# RTC_pb.net
KiCad netlist of a schematic drawn in EAGLE
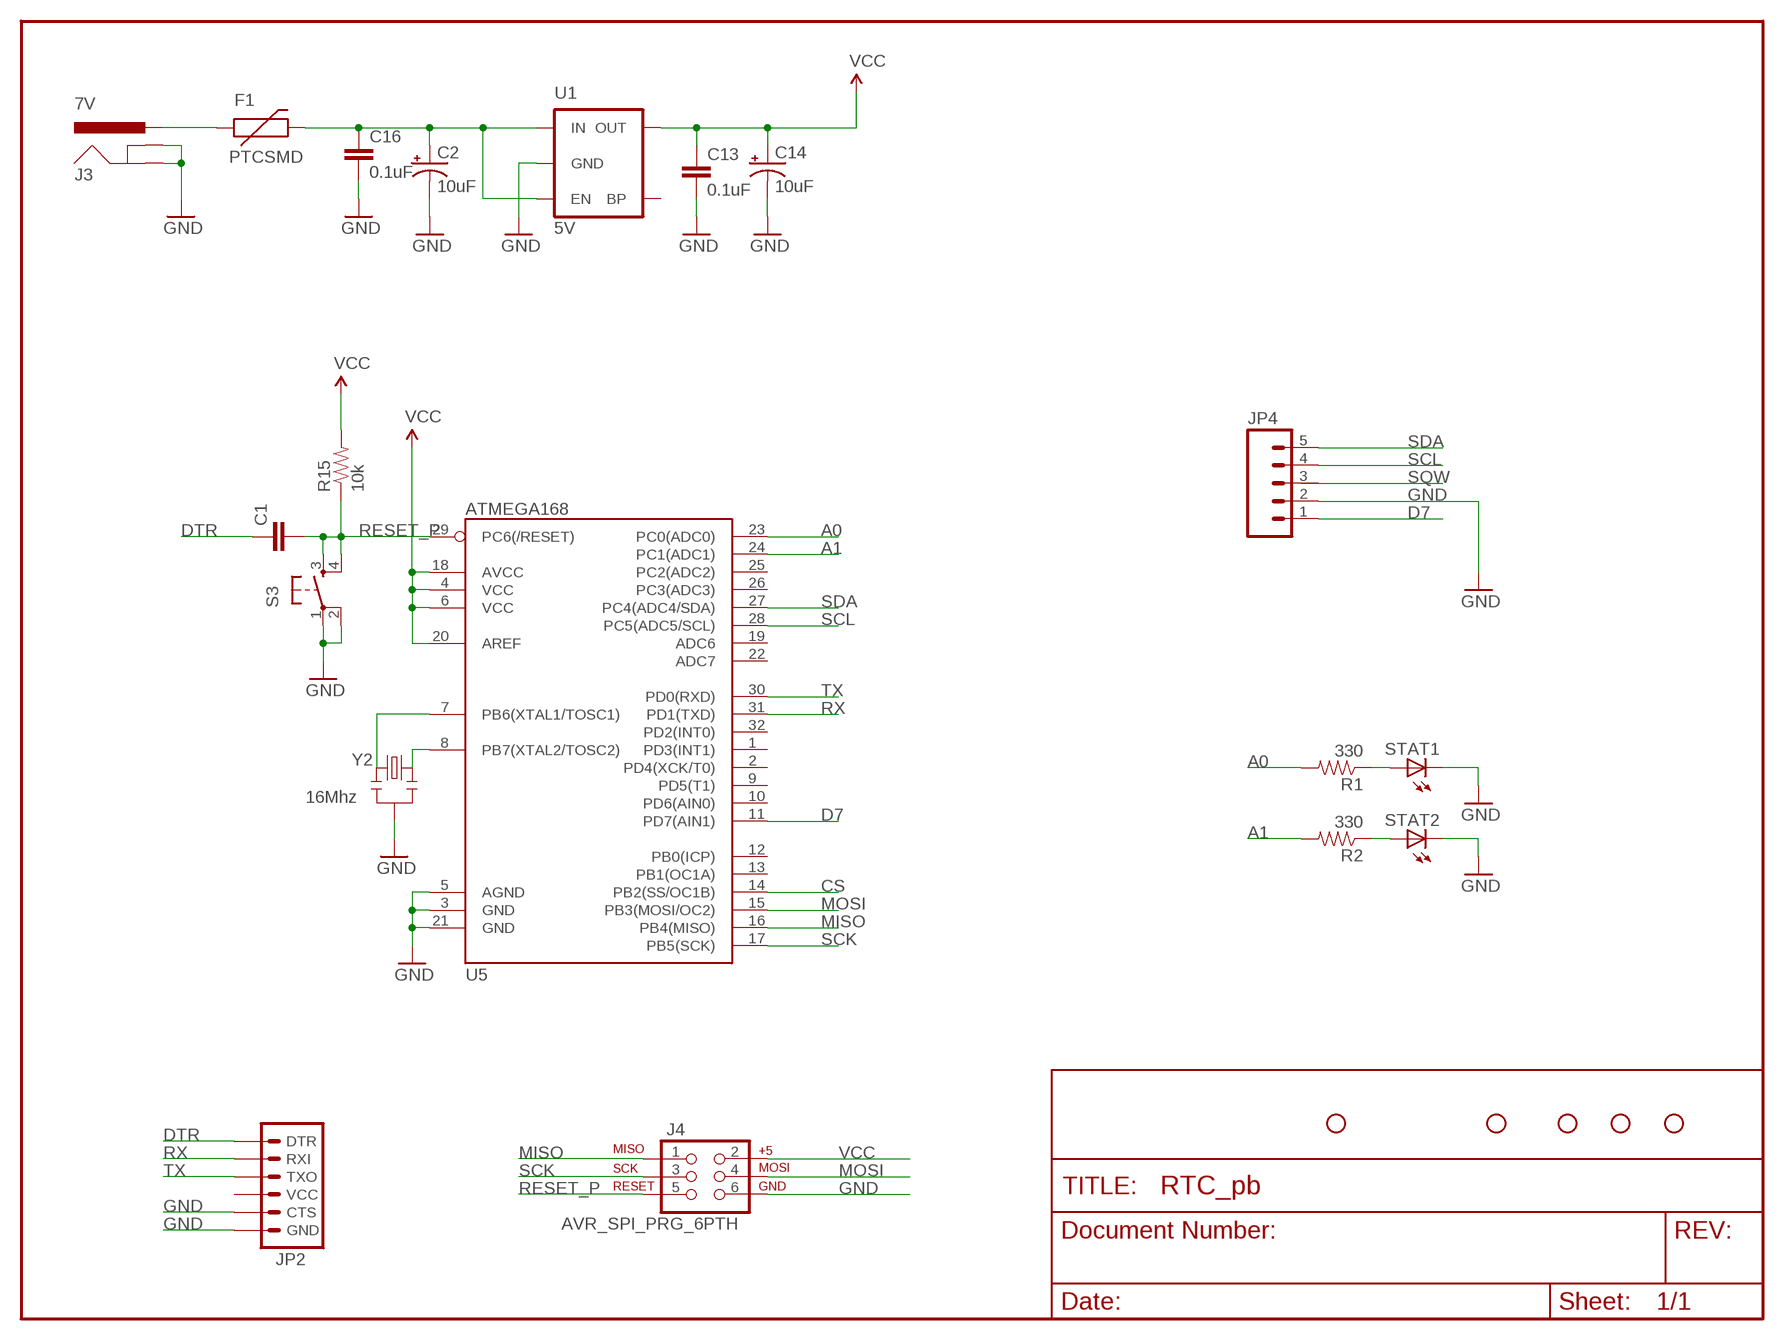
[diagram p0: schematic, sheet 1]

(export (version "E")
  (design (tool "Eeschema 10.0.6"))
  (components
    (comp (ref "C1")
      (value "CAP0603-CAP")
      (footprint "eagle-import:0603-CAP")
      (libsource (lib "eagle-import") (part "CAP0603-CAP"))
    )
    (comp (ref "C2")
      (value "10uF")
      (footprint "eagle-import:EIA3216")
      (libsource (lib "eagle-import") (part "CAP_POL1206"))
    )
    (comp (ref "C13")
      (value "0.1uF")
      (footprint "eagle-import:0603-CAP")
      (libsource (lib "eagle-import") (part "CAP0603-CAP"))
    )
    (comp (ref "C14")
      (value "10uF")
      (footprint "eagle-import:EIA3216")
      (libsource (lib "eagle-import") (part "CAP_POL1206"))
    )
    (comp (ref "C16")
      (value "0.1uF")
      (footprint "eagle-import:0603-CAP")
      (libsource (lib "eagle-import") (part "CAP0603-CAP"))
    )
    (comp (ref "F1")
      (value "PTCSMD")
      (footprint "eagle-import:PTC-1206")
      (libsource (lib "eagle-import") (part "PTCSMD"))
    )
    (comp (ref "J3")
      (value "7V")
      (footprint "eagle-import:POWER_JACK_PTH_LOCK")
      (libsource (lib "eagle-import") (part "POWER_JACKPTH_LOCK"))
    )
    (comp (ref "J4")
      (value "AVR_SPI_PRG_6PTH")
      (footprint "eagle-import:2X3")
      (libsource (lib "eagle-import") (part "AVR_SPI_PRG_6PTH"))
    )
    (comp (ref "JP1")
      (value "STAND-OFFTIGHT")
      (footprint "eagle-import:STAND-OFF-TIGHT")
      (libsource (lib "eagle-import") (part "STAND-OFFTIGHT"))
    )
    (comp (ref "JP2")
      (value "ARDUINO_SERIAL_PROGRAMPTH")
      (footprint "eagle-import:1X06")
      (libsource (lib "eagle-import") (part "ARDUINO_SERIAL_PROGRAMPTH"))
    )
    (comp (ref "JP4")
      (value "M05PTH_LONGPADS")
      (footprint "eagle-import:1X05_LONGPADS")
      (libsource (lib "eagle-import") (part "M05PTH_LONGPADS"))
    )
    (comp (ref "JP7")
      (value "STAND-OFFTIGHT")
      (footprint "eagle-import:STAND-OFF-TIGHT")
      (libsource (lib "eagle-import") (part "STAND-OFFTIGHT"))
    )
    (comp (ref "JP8")
      (value "STAND-OFFTIGHT")
      (footprint "eagle-import:STAND-OFF-TIGHT")
      (libsource (lib "eagle-import") (part "STAND-OFFTIGHT"))
    )
    (comp (ref "JP9")
      (value "STAND-OFFTIGHT")
      (footprint "eagle-import:STAND-OFF-TIGHT")
      (libsource (lib "eagle-import") (part "STAND-OFFTIGHT"))
    )
    (comp (ref "JP10")
      (value "STAND-OFFTIGHT")
      (footprint "eagle-import:STAND-OFF-TIGHT")
      (libsource (lib "eagle-import") (part "STAND-OFFTIGHT"))
    )
    (comp (ref "R1")
      (value "330")
      (footprint "eagle-import:0603-RES")
      (libsource (lib "eagle-import") (part "RESISTOR0603-RES"))
    )
    (comp (ref "R2")
      (value "330")
      (footprint "eagle-import:0603-RES")
      (libsource (lib "eagle-import") (part "RESISTOR0603-RES"))
    )
    (comp (ref "R15")
      (value "10k")
      (footprint "eagle-import:0603-RES")
      (libsource (lib "eagle-import") (part "RESISTOR0603-RES"))
    )
    (comp (ref "S3")
      (value "TAC_SWITCHPTH")
      (footprint "eagle-import:TACTILE-PTH")
      (libsource (lib "eagle-import") (part "TAC_SWITCHPTH"))
    )
    (comp (ref "STAT1")
      (value "Yellow")
      (footprint "eagle-import:LED-1206")
      (libsource (lib "eagle-import") (part "LED1206"))
    )
    (comp (ref "STAT2")
      (value "Yellow")
      (footprint "eagle-import:LED-1206")
      (libsource (lib "eagle-import") (part "LED1206"))
    )
    (comp (ref "U1")
      (value "3.3V")
      (footprint "eagle-import:SOT23-5")
      (libsource (lib "eagle-import") (part "V_REG_LDOSMD"))
    )
    (comp (ref "U5")
      (value "ATMEGA168")
      (footprint "eagle-import:TQFP32-08")
      (libsource (lib "eagle-import") (part "ATMEGA168"))
    )
    (comp (ref "Y2")
      (value "8MHz")
      (footprint "eagle-import:RESONATOR-SMD")
      (libsource (lib "eagle-import") (part "RESONATORSMD"))
    )
  )
  (nets
    (net (code "1") (name "/A0") (class "Default")
      (node (ref "R1") (pin "2") (pinfunction "2_2") (pintype "passive"))
      (node (ref "U5") (pin "23") (pinfunction "PC0(ADC0)_23") (pintype "bidirectional"))
    )
    (net (code "2") (name "/A1") (class "Default")
      (node (ref "R2") (pin "2") (pinfunction "2_2") (pintype "passive"))
      (node (ref "U5") (pin "24") (pinfunction "PC1(ADC1)_24") (pintype "bidirectional"))
    )
    (net (code "3") (name "/CS") (class "Default")
      (node (ref "U5") (pin "14") (pinfunction "PB2(SS/OC1B)_14") (pintype "bidirectional"))
    )
    (net (code "4") (name "/D7") (class "Default")
      (node (ref "JP4") (pin "1") (pinfunction "1_1") (pintype "passive"))
      (node (ref "U5") (pin "11") (pinfunction "PD7(AIN1)_11") (pintype "bidirectional"))
    )
    (net (code "5") (name "/DTR") (class "Default")
      (node (ref "C1") (pin "1") (pinfunction "1_1") (pintype "passive"))
      (node (ref "JP2") (pin "1") (pinfunction "DTR_1") (pintype "passive"))
    )
    (net (code "6") (name "/MISO") (class "Default")
      (node (ref "J4") (pin "1") (pinfunction "1_1") (pintype "passive"))
      (node (ref "U5") (pin "16") (pinfunction "PB4(MISO)_16") (pintype "bidirectional"))
    )
    (net (code "7") (name "/MOSI") (class "Default")
      (node (ref "J4") (pin "4") (pinfunction "4_4") (pintype "passive"))
      (node (ref "U5") (pin "15") (pinfunction "PB3(MOSI/OC2)_15") (pintype "bidirectional"))
    )
    (net (code "8") (name "/RESET_P") (class "Default")
      (node (ref "C1") (pin "2") (pinfunction "2_2") (pintype "passive"))
      (node (ref "J4") (pin "5") (pinfunction "5_5") (pintype "passive"))
      (node (ref "R15") (pin "1") (pinfunction "1_1") (pintype "passive"))
      (node (ref "S3") (pin "3") (pinfunction "3_3") (pintype "passive"))
      (node (ref "S3") (pin "4") (pinfunction "4_4") (pintype "passive"))
      (node (ref "U5") (pin "29") (pinfunction "PC6(/RESET)_29") (pintype "bidirectional"))
    )
    (net (code "9") (name "/RX") (class "Default")
      (node (ref "JP2") (pin "2") (pinfunction "RXI_2") (pintype "passive"))
      (node (ref "U5") (pin "31") (pinfunction "PD1(TXD)_31") (pintype "bidirectional"))
    )
    (net (code "10") (name "/SCK") (class "Default")
      (node (ref "J4") (pin "3") (pinfunction "3_3") (pintype "passive"))
      (node (ref "U5") (pin "17") (pinfunction "PB5(SCK)_17") (pintype "bidirectional"))
    )
    (net (code "11") (name "/SCL") (class "Default")
      (node (ref "JP4") (pin "4") (pinfunction "4_4") (pintype "passive"))
      (node (ref "U5") (pin "28") (pinfunction "PC5(ADC5/SCL)_28") (pintype "bidirectional"))
    )
    (net (code "12") (name "/SDA") (class "Default")
      (node (ref "JP4") (pin "5") (pinfunction "5_5") (pintype "passive"))
      (node (ref "U5") (pin "27") (pinfunction "PC4(ADC4/SDA)_27") (pintype "bidirectional"))
    )
    (net (code "14") (name "/TX") (class "Default")
      (node (ref "JP2") (pin "3") (pinfunction "TXO_3") (pintype "passive"))
      (node (ref "U5") (pin "30") (pinfunction "PD0(RXD)_30") (pintype "bidirectional"))
    )
    (net (code "15") (name "GND") (class "Default")
      (node (ref "C13") (pin "2") (pinfunction "2_2") (pintype "passive"))
      (node (ref "C14") (pin "C") (pinfunction "-_C") (pintype "passive"))
      (node (ref "C16") (pin "2") (pinfunction "2_2") (pintype "passive"))
      (node (ref "C2") (pin "C") (pinfunction "-_C") (pintype "passive"))
      (node (ref "J3") (pin "GND") (pinfunction "GND_GND") (pintype "bidirectional"))
      (node (ref "J3") (pin "GNDBREAK") (pinfunction "GNDBREAK_GNDBREAK") (pintype "bidirectional"))
      (node (ref "J4") (pin "6") (pinfunction "6_6") (pintype "passive"))
      (node (ref "JP2") (pin "5") (pinfunction "CTS_5") (pintype "passive"))
      (node (ref "JP2") (pin "6") (pinfunction "GND_6") (pintype "passive"))
      (node (ref "JP4") (pin "2") (pinfunction "2_2") (pintype "passive"))
      (node (ref "S3") (pin "1") (pinfunction "1_1") (pintype "passive"))
      (node (ref "S3") (pin "2") (pinfunction "2_2") (pintype "passive"))
      (node (ref "STAT1") (pin "C") (pinfunction "C_C") (pintype "passive"))
      (node (ref "STAT2") (pin "C") (pinfunction "C_C") (pintype "passive"))
      (node (ref "U1") (pin "2") (pinfunction "GND_2") (pintype "input"))
      (node (ref "U5") (pin "21") (pinfunction "GND_21") (pintype "bidirectional"))
      (node (ref "U5") (pin "3") (pinfunction "GND_3") (pintype "bidirectional"))
      (node (ref "U5") (pin "5") (pinfunction "AGND_5") (pintype "bidirectional"))
      (node (ref "Y2") (pin "2") (pinfunction "2_2") (pintype "passive"))
    )
    (net (code "16") (name "Net-(C2-+)") (class "Default")
      (node (ref "C16") (pin "1") (pinfunction "1_1") (pintype "passive"))
      (node (ref "C2") (pin "A") (pinfunction "+_A") (pintype "passive"))
      (node (ref "F1") (pin "2") (pinfunction "2_2") (pintype "bidirectional"))
      (node (ref "U1") (pin "1") (pinfunction "IN_1") (pintype "input"))
      (node (ref "U1") (pin "3") (pinfunction "EN_3") (pintype "input"))
    )
    (net (code "17") (name "Net-(F1-Pad1)") (class "Default")
      (node (ref "F1") (pin "1") (pinfunction "1_1") (pintype "bidirectional"))
      (node (ref "J3") (pin "PWR") (pinfunction "PWR_PWR") (pintype "bidirectional"))
    )
    (net (code "18") (name "Net-(R1-Pad1)") (class "Default")
      (node (ref "R1") (pin "1") (pinfunction "1_1") (pintype "passive"))
      (node (ref "STAT1") (pin "A") (pinfunction "A_A") (pintype "passive"))
    )
    (net (code "19") (name "Net-(R2-Pad1)") (class "Default")
      (node (ref "R2") (pin "1") (pinfunction "1_1") (pintype "passive"))
      (node (ref "STAT2") (pin "A") (pinfunction "A_A") (pintype "passive"))
    )
    (net (code "20") (name "Net-(U5-PB6(XTAL1{slash}TOSC1))") (class "Default")
      (node (ref "U5") (pin "7") (pinfunction "PB6(XTAL1/TOSC1)_7") (pintype "bidirectional"))
      (node (ref "Y2") (pin "1") (pinfunction "1_1") (pintype "passive"))
    )
    (net (code "21") (name "Net-(U5-PB7(XTAL2{slash}TOSC2))") (class "Default")
      (node (ref "U5") (pin "8") (pinfunction "PB7(XTAL2/TOSC2)_8") (pintype "bidirectional"))
      (node (ref "Y2") (pin "3") (pinfunction "3_3") (pintype "passive"))
    )
    (net (code "22") (name "VCC") (class "Default")
      (node (ref "C13") (pin "1") (pinfunction "1_1") (pintype "passive"))
      (node (ref "C14") (pin "A") (pinfunction "+_A") (pintype "passive"))
      (node (ref "J4") (pin "2") (pinfunction "2_2") (pintype "passive"))
      (node (ref "R15") (pin "2") (pinfunction "2_2") (pintype "passive"))
      (node (ref "U1") (pin "5") (pinfunction "OUT_5") (pintype "passive"))
      (node (ref "U5") (pin "18") (pinfunction "AVCC_18") (pintype "bidirectional"))
      (node (ref "U5") (pin "20") (pinfunction "AREF_20") (pintype "bidirectional"))
      (node (ref "U5") (pin "4") (pinfunction "VCC_4") (pintype "bidirectional"))
      (node (ref "U5") (pin "6") (pinfunction "VCC_6") (pintype "bidirectional"))
    )
    (net (code "23") (name "unconnected-(JP2-VCC-Pad4)") (class "Default")
      (node (ref "JP2") (pin "4") (pinfunction "VCC_4") (pintype "passive"))
    )
    (net (code "24") (name "unconnected-(JP4-Pad3)") (class "Default")
      (node (ref "JP4") (pin "3") (pinfunction "3_3") (pintype "passive"))
    )
    (net (code "25") (name "unconnected-(U1-BP-Pad4)") (class "Default")
      (node (ref "U1") (pin "4") (pinfunction "BP_4") (pintype "input"))
    )
    (net (code "26") (name "unconnected-(U5-ADC6-Pad19)") (class "Default")
      (node (ref "U5") (pin "19") (pinfunction "ADC6_19") (pintype "bidirectional"))
    )
    (net (code "27") (name "unconnected-(U5-ADC7-Pad22)") (class "Default")
      (node (ref "U5") (pin "22") (pinfunction "ADC7_22") (pintype "bidirectional"))
    )
    (net (code "28") (name "unconnected-(U5-PB0(ICP)-Pad12)") (class "Default")
      (node (ref "U5") (pin "12") (pinfunction "PB0(ICP)_12") (pintype "bidirectional"))
    )
    (net (code "29") (name "unconnected-(U5-PB1(OC1A)-Pad13)") (class "Default")
      (node (ref "U5") (pin "13") (pinfunction "PB1(OC1A)_13") (pintype "bidirectional"))
    )
    (net (code "30") (name "unconnected-(U5-PC2(ADC2)-Pad25)") (class "Default")
      (node (ref "U5") (pin "25") (pinfunction "PC2(ADC2)_25") (pintype "bidirectional"))
    )
    (net (code "31") (name "unconnected-(U5-PC3(ADC3)-Pad26)") (class "Default")
      (node (ref "U5") (pin "26") (pinfunction "PC3(ADC3)_26") (pintype "bidirectional"))
    )
    (net (code "32") (name "unconnected-(U5-PD2(INT0)-Pad32)") (class "Default")
      (node (ref "U5") (pin "32") (pinfunction "PD2(INT0)_32") (pintype "bidirectional"))
    )
    (net (code "33") (name "unconnected-(U5-PD3(INT1)-Pad1)") (class "Default")
      (node (ref "U5") (pin "1") (pinfunction "PD3(INT1)_1") (pintype "bidirectional"))
    )
    (net (code "34") (name "unconnected-(U5-PD4(XCK{slash}T0)-Pad2)") (class "Default")
      (node (ref "U5") (pin "2") (pinfunction "PD4(XCK/T0)_2") (pintype "bidirectional"))
    )
    (net (code "35") (name "unconnected-(U5-PD5(T1)-Pad9)") (class "Default")
      (node (ref "U5") (pin "9") (pinfunction "PD5(T1)_9") (pintype "bidirectional"))
    )
    (net (code "36") (name "unconnected-(U5-PD6(AIN0)-Pad10)") (class "Default")
      (node (ref "U5") (pin "10") (pinfunction "PD6(AIN0)_10") (pintype "bidirectional"))
    )
  )
)
